# source_eagle.net
KiCad netlist of a schematic drawn in EAGLE
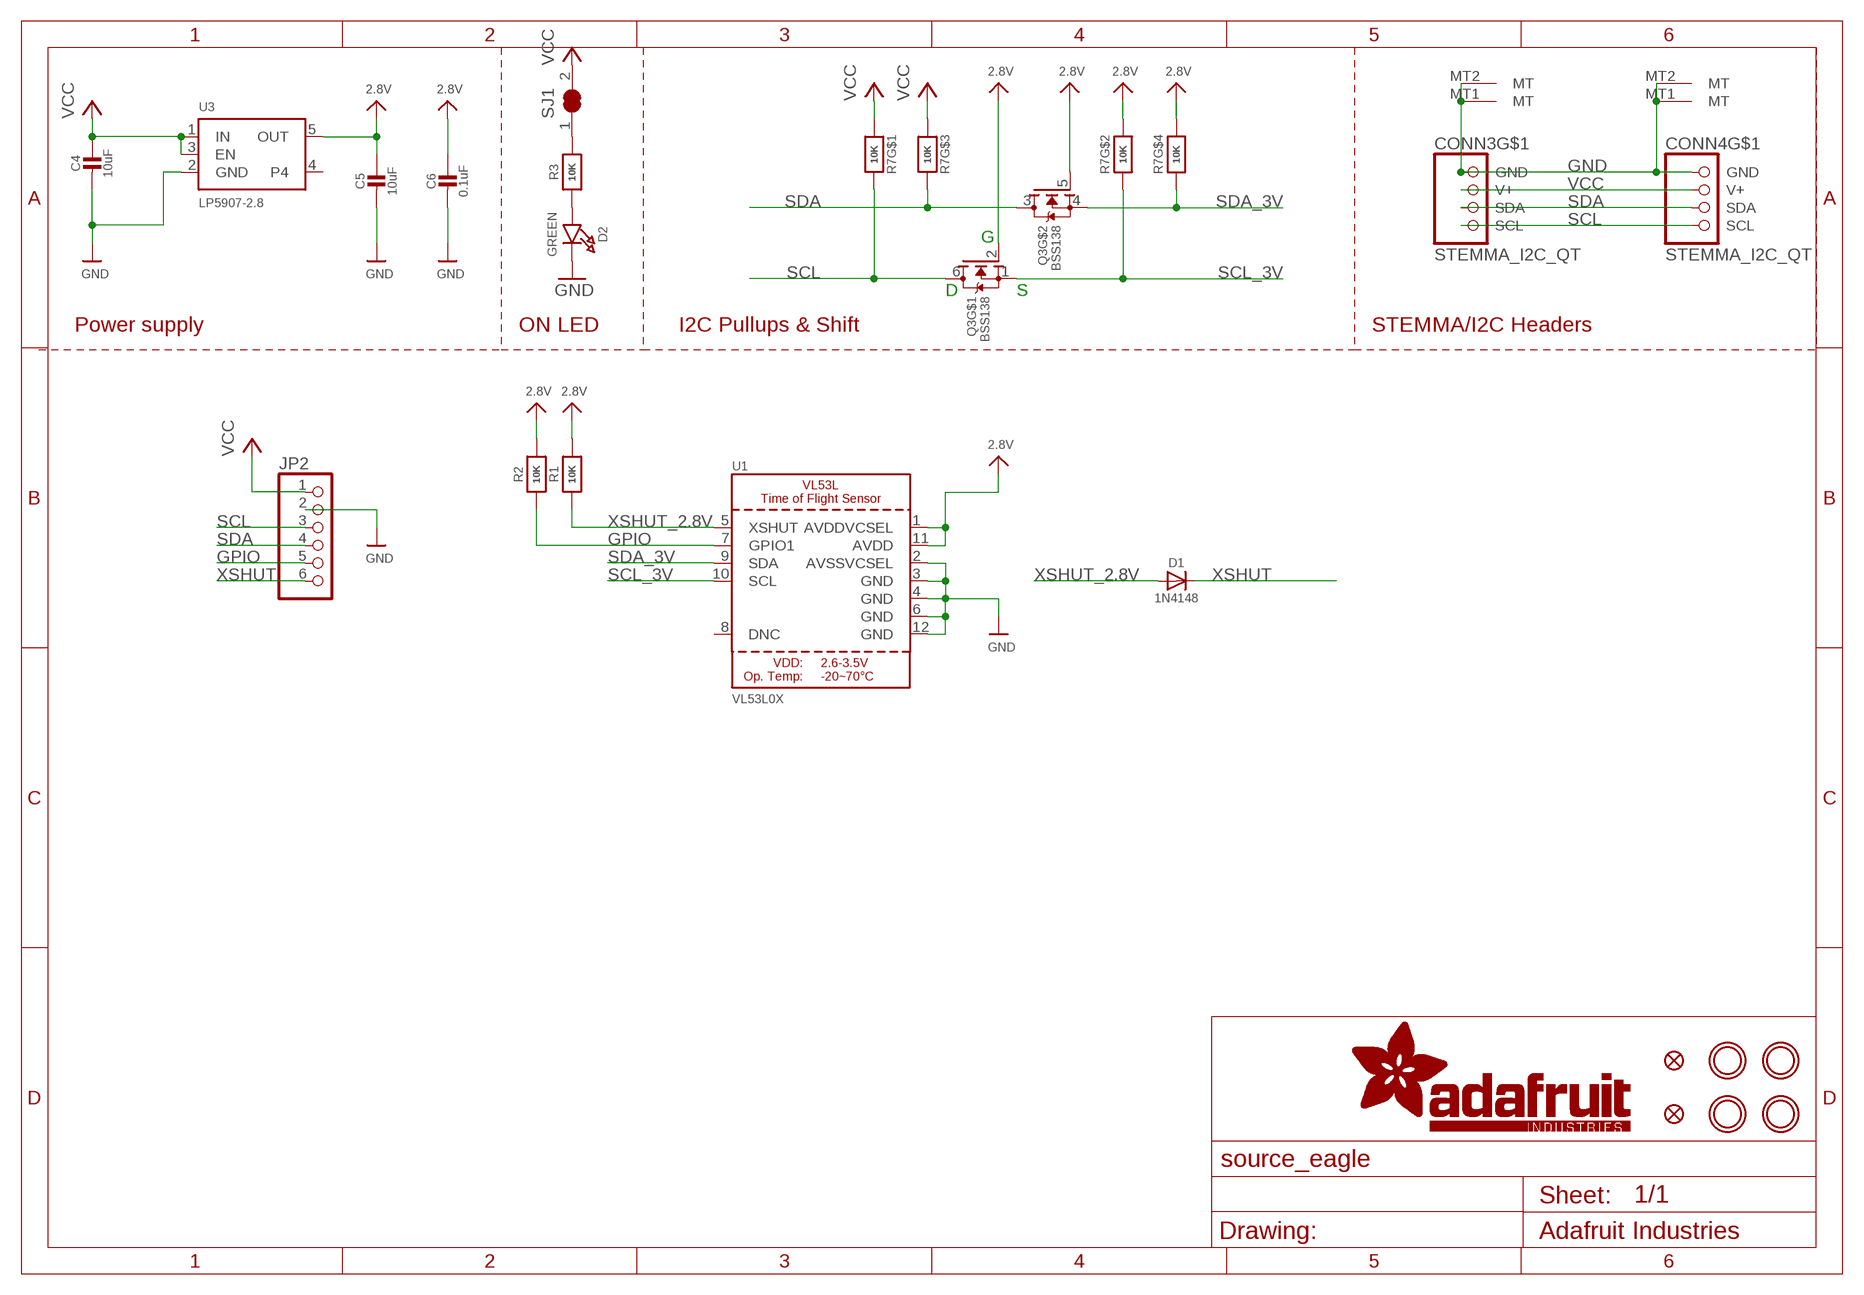
[diagram p0: schematic, sheet 1]

(export (version "E")
  (design (tool "Eeschema 10.0.6"))
  (components
    (comp (ref "C4")
      (value "10uF")
      (footprint "eagle-import:0805-NO")
      (libsource (lib "eagle-import") (part "CAP_CERAMIC0805-NOOUTLINE"))
    )
    (comp (ref "C5")
      (value "10uF")
      (footprint "eagle-import:0805-NO")
      (libsource (lib "eagle-import") (part "CAP_CERAMIC0805-NOOUTLINE"))
    )
    (comp (ref "C6")
      (value "0.1uF")
      (footprint "eagle-import:0603-NO")
      (libsource (lib "eagle-import") (part "CAP_CERAMIC0603_NO"))
    )
    (comp (ref "CONN3")
      (value "STEMMA_I2C_QT")
      (footprint "eagle-import:JST_SH4")
      (libsource (lib "eagle-import") (part "STEMMA_I2C_QT"))
    )
    (comp (ref "CONN4")
      (value "STEMMA_I2C_QT")
      (footprint "eagle-import:JST_SH4")
      (libsource (lib "eagle-import") (part "STEMMA_I2C_QT"))
    )
    (comp (ref "D1")
      (value "1N4148")
      (footprint "eagle-import:SOD-323")
      (libsource (lib "eagle-import") (part "DIODESOD-323"))
    )
    (comp (ref "D2")
      (value "GREEN")
      (footprint "eagle-import:CHIPLED_0603_NOOUTLINE")
      (libsource (lib "eagle-import") (part "LED0603_NOOUTLINE"))
    )
    (comp (ref "FID1")
      (value "FIDUCIAL_1MM")
      (footprint "eagle-import:FIDUCIAL_1MM")
      (libsource (lib "eagle-import") (part "FIDUCIAL_1MM"))
    )
    (comp (ref "FID4")
      (value "FIDUCIAL_1MM")
      (footprint "eagle-import:FIDUCIAL_1MM")
      (libsource (lib "eagle-import") (part "FIDUCIAL_1MM"))
    )
    (comp (ref "JP2")
      (value "HEADER-1X670MIL")
      (footprint "eagle-import:1X06_ROUND_70")
      (libsource (lib "eagle-import") (part "HEADER-1X670MIL"))
    )
    (comp (ref "Q3")
      (value "BSS138")
      (footprint "eagle-import:SOT363")
      (libsource (lib "eagle-import") (part "MOSFET-N_DUAL"))
    )
    (comp (ref "R1")
      (value "10K")
      (footprint "eagle-import:0603-NO")
      (libsource (lib "eagle-import") (part "RESISTOR_0603_NOOUT"))
    )
    (comp (ref "R2")
      (value "10K")
      (footprint "eagle-import:0603-NO")
      (libsource (lib "eagle-import") (part "RESISTOR_0603_NOOUT"))
    )
    (comp (ref "R3")
      (value "10K")
      (footprint "eagle-import:0603-NO")
      (libsource (lib "eagle-import") (part "RESISTOR_0603_NOOUT"))
    )
    (comp (ref "R7")
      (value "10K")
      (footprint "eagle-import:RESPACK_4X0603")
      (libsource (lib "eagle-import") (part "RESISTOR_4PACK"))
    )
    (comp (ref "SJ1")
      (value "SOLDERJUMPER_CLOSED")
      (footprint "eagle-import:SOLDERJUMPER_CLOSEDWIRE")
      (libsource (lib "eagle-import") (part "SOLDERJUMPER_CLOSED"))
    )
    (comp (ref "U$30")
      (value "MOUNTINGHOLE2.5")
      (footprint "eagle-import:MOUNTINGHOLE_2.5_PLATED")
      (libsource (lib "eagle-import") (part "MOUNTINGHOLE2.5"))
    )
    (comp (ref "U$31")
      (value "MOUNTINGHOLE2.5")
      (footprint "eagle-import:MOUNTINGHOLE_2.5_PLATED")
      (libsource (lib "eagle-import") (part "MOUNTINGHOLE2.5"))
    )
    (comp (ref "U$33")
      (value "MOUNTINGHOLE2.5")
      (footprint "eagle-import:MOUNTINGHOLE_2.5_PLATED")
      (libsource (lib "eagle-import") (part "MOUNTINGHOLE2.5"))
    )
    (comp (ref "U$34")
      (value "MOUNTINGHOLE2.5")
      (footprint "eagle-import:MOUNTINGHOLE_2.5_PLATED")
      (libsource (lib "eagle-import") (part "MOUNTINGHOLE2.5"))
    )
    (comp (ref "U1")
      (value "VL53L0X")
      (footprint "eagle-import:LGA12_ST")
      (libsource (lib "eagle-import") (part "VL53L0X"))
    )
    (comp (ref "U3")
      (value "LP5907-2.8")
      (footprint "eagle-import:SOT23-5")
      (libsource (lib "eagle-import") (part "VREG_SOT23-5"))
    )
  )
  (nets
    (net (code "1") (name "/GPIO") (class "Default")
      (node (ref "JP2") (pin "5") (pinfunction "5_5") (pintype "passive"))
      (node (ref "R2") (pin "1") (pinfunction "1_1") (pintype "passive"))
      (node (ref "U1") (pin "7") (pinfunction "GPIO1_7") (pintype "output"))
    )
    (net (code "2") (name "/SCL") (class "Default")
      (node (ref "CONN3") (pin "4") (pinfunction "SCL_4") (pintype "passive"))
      (node (ref "CONN4") (pin "4") (pinfunction "SCL_4") (pintype "passive"))
      (node (ref "JP2") (pin "3") (pinfunction "3_3") (pintype "passive"))
      (node (ref "Q3") (pin "6") (pinfunction "D_6") (pintype "bidirectional"))
      (node (ref "R7") (pin "8") (pinfunction "2_8") (pintype "passive"))
    )
    (net (code "3") (name "/SCL_3V") (class "Default")
      (node (ref "Q3") (pin "1") (pinfunction "S_1") (pintype "bidirectional"))
      (node (ref "R7") (pin "7") (pinfunction "2_7") (pintype "passive"))
      (node (ref "U1") (pin "10") (pinfunction "SCL_10") (pintype "open_collector"))
    )
    (net (code "4") (name "/SDA") (class "Default")
      (node (ref "CONN3") (pin "3") (pinfunction "SDA_3") (pintype "passive"))
      (node (ref "CONN4") (pin "3") (pinfunction "SDA_3") (pintype "passive"))
      (node (ref "JP2") (pin "4") (pinfunction "4_4") (pintype "passive"))
      (node (ref "Q3") (pin "3") (pinfunction "D_3") (pintype "bidirectional"))
      (node (ref "R7") (pin "6") (pinfunction "2_6") (pintype "passive"))
    )
    (net (code "5") (name "/SDA_3V") (class "Default")
      (node (ref "Q3") (pin "4") (pinfunction "S_4") (pintype "bidirectional"))
      (node (ref "R7") (pin "5") (pinfunction "2_5") (pintype "passive"))
      (node (ref "U1") (pin "9") (pinfunction "SDA_9") (pintype "open_collector"))
    )
    (net (code "6") (name "/XSHUT") (class "Default")
      (node (ref "D1") (pin "C") (pinfunction "C_C") (pintype "passive"))
      (node (ref "JP2") (pin "6") (pinfunction "6_6") (pintype "passive"))
    )
    (net (code "7") (name "/XSHUT_2.8V") (class "Default")
      (node (ref "D1") (pin "A") (pinfunction "A_A") (pintype "passive"))
      (node (ref "R1") (pin "1") (pinfunction "1_1") (pintype "passive"))
      (node (ref "U1") (pin "5") (pinfunction "XSHUT_5") (pintype "input"))
    )
    (net (code "8") (name "2.8V") (class "Default")
      (node (ref "C5") (pin "1") (pinfunction "1_1") (pintype "passive"))
      (node (ref "C6") (pin "1") (pinfunction "1_1") (pintype "passive"))
      (node (ref "Q3") (pin "2") (pinfunction "G_2") (pintype "bidirectional"))
      (node (ref "Q3") (pin "5") (pinfunction "G_5") (pintype "bidirectional"))
      (node (ref "R1") (pin "2") (pinfunction "2_2") (pintype "passive"))
      (node (ref "R2") (pin "2") (pinfunction "2_2") (pintype "passive"))
      (node (ref "R7") (pin "2") (pinfunction "1_2") (pintype "passive"))
      (node (ref "R7") (pin "4") (pinfunction "1_4") (pintype "passive"))
      (node (ref "U1") (pin "1") (pinfunction "AVDDVCSEL_1") (pintype "power_in"))
      (node (ref "U1") (pin "11") (pinfunction "AVDD_11") (pintype "power_in"))
      (node (ref "U3") (pin "5") (pinfunction "OUT_5") (pintype "power_in"))
    )
    (net (code "9") (name "GND") (class "Default")
      (node (ref "C4") (pin "2") (pinfunction "2_2") (pintype "passive"))
      (node (ref "C5") (pin "2") (pinfunction "2_2") (pintype "passive"))
      (node (ref "C6") (pin "2") (pinfunction "2_2") (pintype "passive"))
      (node (ref "CONN3") (pin "1") (pinfunction "GND_1") (pintype "passive"))
      (node (ref "CONN3") (pin "MT1") (pinfunction "MT_MT1") (pintype "bidirectional"))
      (node (ref "CONN3") (pin "MT2") (pinfunction "MT_MT2") (pintype "bidirectional"))
      (node (ref "CONN4") (pin "1") (pinfunction "GND_1") (pintype "passive"))
      (node (ref "CONN4") (pin "MT1") (pinfunction "MT_MT1") (pintype "bidirectional"))
      (node (ref "CONN4") (pin "MT2") (pinfunction "MT_MT2") (pintype "bidirectional"))
      (node (ref "D2") (pin "C") (pinfunction "C_C") (pintype "passive"))
      (node (ref "JP2") (pin "2") (pinfunction "2_2") (pintype "passive"))
      (node (ref "U1") (pin "12") (pinfunction "GND_12") (pintype "power_in"))
      (node (ref "U1") (pin "2") (pinfunction "AVSSVCSEL_2") (pintype "power_in"))
      (node (ref "U1") (pin "3") (pinfunction "GND_3") (pintype "power_in"))
      (node (ref "U1") (pin "4") (pinfunction "GND_4") (pintype "power_in"))
      (node (ref "U1") (pin "6") (pinfunction "GND_6") (pintype "power_in"))
      (node (ref "U3") (pin "2") (pinfunction "GND_2") (pintype "power_in"))
    )
    (net (code "10") (name "Net-(D2-PadA)") (class "Default")
      (node (ref "D2") (pin "A") (pinfunction "A_A") (pintype "passive"))
      (node (ref "R3") (pin "1") (pinfunction "1_1") (pintype "passive"))
    )
    (net (code "11") (name "Net-(R3-Pad2)") (class "Default")
      (node (ref "R3") (pin "2") (pinfunction "2_2") (pintype "passive"))
      (node (ref "SJ1") (pin "1") (pinfunction "1_1") (pintype "passive"))
    )
    (net (code "12") (name "VCC") (class "Default")
      (node (ref "C4") (pin "1") (pinfunction "1_1") (pintype "passive"))
      (node (ref "CONN3") (pin "2") (pinfunction "V+_2") (pintype "passive"))
      (node (ref "CONN4") (pin "2") (pinfunction "V+_2") (pintype "passive"))
      (node (ref "JP2") (pin "1") (pinfunction "1_1") (pintype "passive"))
      (node (ref "R7") (pin "1") (pinfunction "1_1") (pintype "passive"))
      (node (ref "R7") (pin "3") (pinfunction "1_3") (pintype "passive"))
      (node (ref "SJ1") (pin "2") (pinfunction "2_2") (pintype "passive"))
      (node (ref "U3") (pin "1") (pinfunction "IN_1") (pintype "power_in"))
      (node (ref "U3") (pin "3") (pinfunction "EN_3") (pintype "input"))
    )
    (net (code "13") (name "unconnected-(U1-DNC-Pad8)") (class "Default")
      (node (ref "U1") (pin "8") (pinfunction "DNC_8") (pintype "no_connect"))
    )
    (net (code "14") (name "unconnected-(U3-P4-Pad4)") (class "Default")
      (node (ref "U3") (pin "4") (pinfunction "P4_4") (pintype "bidirectional"))
    )
  )
)
